# bpod_stepper_1_4_5.net
KiCad netlist of a schematic drawn in EAGLE
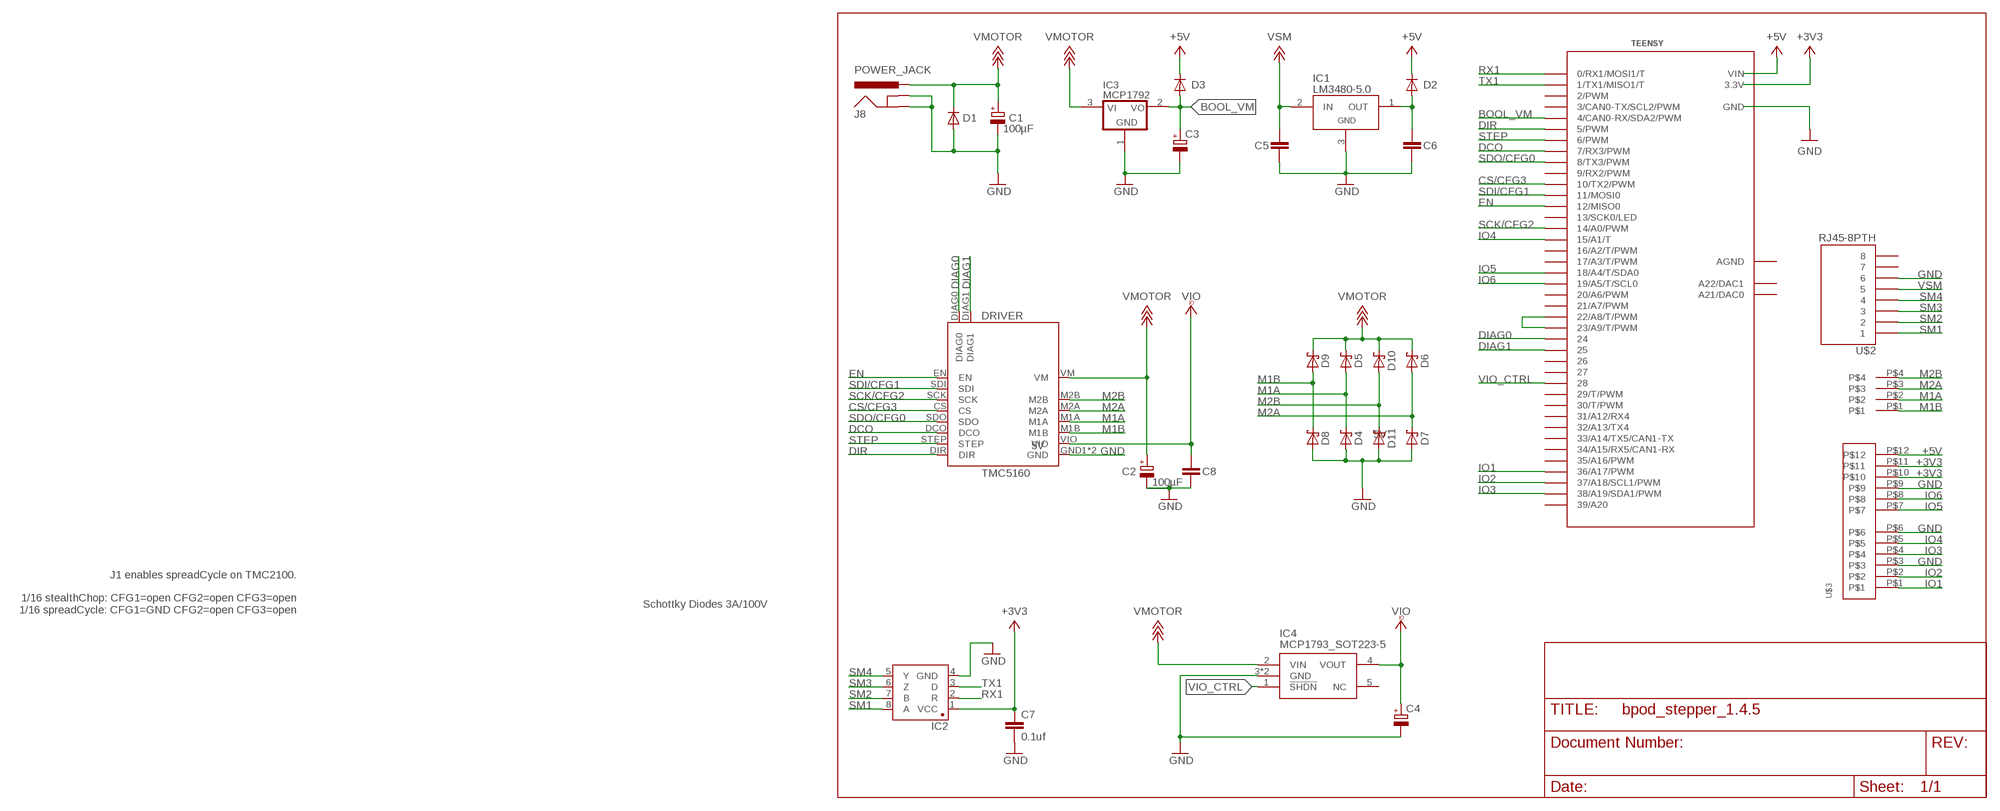
[diagram p0: schematic, sheet 1]

(export (version "E")
  (design (tool "Eeschema 10.0.6"))
  (components
    (comp (ref "C1")
      (value "100µF")
      (footprint "eagle-import:PANASONIC_G")
      (libsource (lib "eagle-import") (part "CPOL-EUG"))
    )
    (comp (ref "C2")
      (value "100µF")
      (footprint "eagle-import:PANASONIC_G")
      (libsource (lib "eagle-import") (part "CPOL-EUG"))
    )
    (comp (ref "C3")
      (value "CPOL-EUB")
      (footprint "eagle-import:PANASONIC_B")
      (libsource (lib "eagle-import") (part "CPOL-EUB"))
    )
    (comp (ref "C4")
      (value "CPOL-EUB")
      (footprint "eagle-import:PANASONIC_B")
      (libsource (lib "eagle-import") (part "CPOL-EUB"))
    )
    (comp (ref "C5")
      (value "0.1uf")
      (footprint "eagle-import:1206@1")
      (libsource (lib "eagle-import") (part "CAP1206"))
    )
    (comp (ref "C6")
      (value "0.1uf")
      (footprint "eagle-import:1206@1")
      (libsource (lib "eagle-import") (part "CAP1206"))
    )
    (comp (ref "C7")
      (value "0.1uf")
      (footprint "eagle-import:1206@1")
      (libsource (lib "eagle-import") (part "CAP1206"))
    )
    (comp (ref "C8")
      (value "100nf")
      (footprint "eagle-import:1206@1")
      (libsource (lib "eagle-import") (part "CAP1206"))
    )
    (comp (ref "D1")
      (value "DIODE-DO214AA")
      (footprint "eagle-import:DO214AA")
      (libsource (lib "eagle-import") (part "DIODE-DO214AA"))
    )
    (comp (ref "D2")
      (value "MBR0520LT")
      (footprint "eagle-import:SOD123")
      (libsource (lib "eagle-import") (part "MBR0520LT"))
    )
    (comp (ref "D3")
      (value "MBR0520LT")
      (footprint "eagle-import:SOD123")
      (libsource (lib "eagle-import") (part "MBR0520LT"))
    )
    (comp (ref "D4")
      (value "S310FA")
      (footprint "eagle-import:SOD123")
      (libsource (lib "eagle-import") (part "D_SCHOTTKY-SOD123"))
    )
    (comp (ref "D5")
      (value "S310FA")
      (footprint "eagle-import:SOD123")
      (libsource (lib "eagle-import") (part "D_SCHOTTKY-SOD123"))
    )
    (comp (ref "D6")
      (value "S310FA")
      (footprint "eagle-import:SOD123")
      (libsource (lib "eagle-import") (part "D_SCHOTTKY-SOD123"))
    )
    (comp (ref "D7")
      (value "S310FA")
      (footprint "eagle-import:SOD123")
      (libsource (lib "eagle-import") (part "D_SCHOTTKY-SOD123"))
    )
    (comp (ref "D8")
      (value "S310FA")
      (footprint "eagle-import:SOD123")
      (libsource (lib "eagle-import") (part "D_SCHOTTKY-SOD123"))
    )
    (comp (ref "D9")
      (value "S310FA")
      (footprint "eagle-import:SOD123")
      (libsource (lib "eagle-import") (part "D_SCHOTTKY-SOD123"))
    )
    (comp (ref "D10")
      (value "S310FA")
      (footprint "eagle-import:SOD123")
      (libsource (lib "eagle-import") (part "D_SCHOTTKY-SOD123"))
    )
    (comp (ref "D11")
      (value "S310FA")
      (footprint "eagle-import:SOD123")
      (libsource (lib "eagle-import") (part "D_SCHOTTKY-SOD123"))
    )
    (comp (ref "DRIVER")
      (value "TMC5160")
      (footprint "eagle-import:TMC5160")
      (libsource (lib "eagle-import") (part "TMC5160"))
    )
    (comp (ref "IC1")
      (value "LM3480-5.0")
      (footprint "eagle-import:SOT-23-3")
      (libsource (lib "eagle-import") (part "LM3480-5.0"))
    )
    (comp (ref "IC2")
      (value "SN65HVD31DR")
      (footprint "eagle-import:SO08")
      (libsource (lib "eagle-import") (part "SN65HVD31DR"))
    )
    (comp (ref "IC3")
      (value "MCP1792")
      (footprint "eagle-import:SOT23A_MICROCHIP_CB")
      (libsource (lib "eagle-import") (part "MCP170302E/CB-12"))
    )
    (comp (ref "IC4")
      (value "MCP1793_SOT223-5")
      (footprint "eagle-import:SOT223-5")
      (libsource (lib "eagle-import") (part "MCP1793_SOT223-5"))
    )
    (comp (ref "J8")
      (value "POWER_JACK")
      (footprint "eagle-import:POWER_JACK_PTH")
      (libsource (lib "eagle-import") (part "POWER_JACK"))
    )
    (comp (ref "TEENSY")
      (value "TEENSY_3.6_DIL")
      (footprint "eagle-import:TEENSY_3.6_DIL")
      (libsource (lib "eagle-import") (part "TEENSY_3.6_DIL"))
    )
    (comp (ref "U$2")
      (value "RJ45-8PTH")
      (footprint "eagle-import:RJ45-8")
      (libsource (lib "eagle-import") (part "RJ45-8PTH"))
    )
    (comp (ref "U$3")
      (value "12POS_MOLEX_SOCKET")
      (footprint "eagle-import:12POS_MOLEX_SOCKET")
      (libsource (lib "eagle-import") (part "12POS_MOLEX_SOCKET"))
    )
    (comp (ref "U$4")
      (value "MOLEX395221004")
      (footprint "eagle-import:MOLEX395221004")
      (libsource (lib "eagle-import") (part "MOLEX395221004"))
    )
  )
  (nets
    (net (code "1") (name "+3V3") (class "Default")
      (node (ref "C7") (pin "1") (pinfunction "1_1") (pintype "passive"))
      (node (ref "IC2") (pin "1") (pinfunction "VCC_1") (pintype "bidirectional"))
      (node (ref "TEENSY") (pin "3.3V") (pinfunction "3.3V_3.3V") (pintype "power_in"))
      (node (ref "TEENSY") (pin "3.3V3") (pinfunction "3.3V_3.3V3") (pintype "power_in"))
      (node (ref "U$3") (pin "P$10") (pinfunction "P$10_P$10") (pintype "bidirectional"))
      (node (ref "U$3") (pin "P$11") (pinfunction "P$11_P$11") (pintype "bidirectional"))
    )
    (net (code "2") (name "+5V") (class "Default")
      (node (ref "D2") (pin "C") (pinfunction "C_C") (pintype "passive"))
      (node (ref "D3") (pin "C") (pinfunction "C_C") (pintype "passive"))
      (node (ref "TEENSY") (pin "VIN") (pinfunction "VIN_VIN") (pintype "power_in"))
      (node (ref "U$3") (pin "P$12") (pinfunction "P$12_P$12") (pintype "bidirectional"))
    )
    (net (code "3") (name "+12V") (class "Default")
      (node (ref "C5") (pin "2") (pinfunction "2_2") (pintype "passive"))
      (node (ref "IC1") (pin "2") (pinfunction "IN_2") (pintype "power_in"))
      (node (ref "U$2") (pin "5") (pinfunction "5_5") (pintype "bidirectional"))
    )
    (net (code "4") (name "+18V") (class "Default")
      (node (ref "C1") (pin "+") (pinfunction "+_+") (pintype "passive"))
      (node (ref "C2") (pin "+") (pinfunction "+_+") (pintype "passive"))
      (node (ref "D1") (pin "C") (pinfunction "C_C") (pintype "passive"))
      (node (ref "D10") (pin "C") (pinfunction "C_C") (pintype "passive"))
      (node (ref "D5") (pin "C") (pinfunction "C_C") (pintype "passive"))
      (node (ref "D6") (pin "C") (pinfunction "C_C") (pintype "passive"))
      (node (ref "D9") (pin "C") (pinfunction "C_C") (pintype "passive"))
      (node (ref "DRIVER") (pin "VM") (pinfunction "VM_VM") (pintype "power_in"))
      (node (ref "IC3") (pin "3") (pinfunction "VI_3") (pintype "power_in"))
      (node (ref "IC4") (pin "2") (pinfunction "VIN_2") (pintype "bidirectional"))
      (node (ref "J8") (pin "PWR") (pinfunction "PWR_PWR") (pintype "bidirectional"))
    )
    (net (code "5") (name "/AGND") (class "Default")
      (node (ref "TEENSY") (pin "AGND") (pinfunction "AGND_AGND") (pintype "power_in"))
    )
    (net (code "6") (name "/CS{slash}CFG3") (class "Default")
      (node (ref "DRIVER") (pin "CS") (pinfunction "CS_CS") (pintype "passive"))
      (node (ref "TEENSY") (pin "10") (pinfunction "10/TX2/PWM_10") (pintype "bidirectional"))
    )
    (net (code "7") (name "/DCO") (class "Default")
      (node (ref "DRIVER") (pin "DCO") (pinfunction "DCO_DCO") (pintype "passive"))
      (node (ref "TEENSY") (pin "7") (pinfunction "7/RX3/PWM_7") (pintype "bidirectional"))
    )
    (net (code "8") (name "/DIAG0") (class "Default")
      (node (ref "DRIVER") (pin "DIAG0") (pinfunction "DIAG0_DIAG0") (pintype "passive"))
      (node (ref "TEENSY") (pin "24") (pinfunction "24_24") (pintype "bidirectional"))
    )
    (net (code "9") (name "/DIAG1") (class "Default")
      (node (ref "DRIVER") (pin "DIAG1") (pinfunction "DIAG1_DIAG1") (pintype "passive"))
      (node (ref "TEENSY") (pin "25") (pinfunction "25_25") (pintype "bidirectional"))
    )
    (net (code "10") (name "/DIR") (class "Default")
      (node (ref "DRIVER") (pin "DIR") (pinfunction "DIR_DIR") (pintype "input"))
      (node (ref "TEENSY") (pin "5") (pinfunction "5/PWM_5") (pintype "bidirectional"))
    )
    (net (code "11") (name "/EN") (class "Default")
      (node (ref "DRIVER") (pin "EN") (pinfunction "EN_EN") (pintype "passive"))
      (node (ref "TEENSY") (pin "12") (pinfunction "12/MISO0_12") (pintype "bidirectional"))
    )
    (net (code "12") (name "/IO1") (class "Default")
      (node (ref "TEENSY") (pin "36/A17") (pinfunction "36/A17/PWM_36/A17") (pintype "bidirectional"))
      (node (ref "U$3") (pin "P$1") (pinfunction "P$1_P$1") (pintype "bidirectional"))
    )
    (net (code "13") (name "/IO2") (class "Default")
      (node (ref "TEENSY") (pin "37/A18") (pinfunction "37/A18/SCL1/PWM_37/A18") (pintype "bidirectional"))
      (node (ref "U$3") (pin "P$2") (pinfunction "P$2_P$2") (pintype "bidirectional"))
    )
    (net (code "14") (name "/IO3") (class "Default")
      (node (ref "TEENSY") (pin "38/A19") (pinfunction "38/A19/SDA1/PWM_38/A19") (pintype "bidirectional"))
      (node (ref "U$3") (pin "P$4") (pinfunction "P$4_P$4") (pintype "bidirectional"))
    )
    (net (code "15") (name "/IO4") (class "Default")
      (node (ref "TEENSY") (pin "15/A1") (pinfunction "15/A1/T_15/A1") (pintype "bidirectional"))
      (node (ref "U$3") (pin "P$5") (pinfunction "P$5_P$5") (pintype "bidirectional"))
    )
    (net (code "16") (name "/IO5") (class "Default")
      (node (ref "TEENSY") (pin "18/A4") (pinfunction "18/A4/T/SDA0_18/A4") (pintype "bidirectional"))
      (node (ref "U$3") (pin "P$7") (pinfunction "P$7_P$7") (pintype "bidirectional"))
    )
    (net (code "17") (name "/IO6") (class "Default")
      (node (ref "TEENSY") (pin "19/A5") (pinfunction "19/A5/T/SCL0_19/A5") (pintype "bidirectional"))
      (node (ref "U$3") (pin "P$8") (pinfunction "P$8_P$8") (pintype "bidirectional"))
    )
    (net (code "18") (name "/M1A") (class "Default")
      (node (ref "D4") (pin "C") (pinfunction "C_C") (pintype "passive"))
      (node (ref "D5") (pin "A") (pinfunction "A_A") (pintype "passive"))
      (node (ref "DRIVER") (pin "M1A") (pinfunction "M1A_M1A") (pintype "output"))
      (node (ref "U$4") (pin "P$2") (pinfunction "P$2_P$2") (pintype "bidirectional"))
    )
    (net (code "19") (name "/M1B") (class "Default")
      (node (ref "D8") (pin "C") (pinfunction "C_C") (pintype "passive"))
      (node (ref "D9") (pin "A") (pinfunction "A_A") (pintype "passive"))
      (node (ref "DRIVER") (pin "M1B") (pinfunction "M1B_M1B") (pintype "output"))
      (node (ref "U$4") (pin "P$1") (pinfunction "P$1_P$1") (pintype "bidirectional"))
    )
    (net (code "20") (name "/M2A") (class "Default")
      (node (ref "D6") (pin "A") (pinfunction "A_A") (pintype "passive"))
      (node (ref "D7") (pin "C") (pinfunction "C_C") (pintype "passive"))
      (node (ref "DRIVER") (pin "M2A") (pinfunction "M2A_M2A") (pintype "output"))
      (node (ref "U$4") (pin "P$3") (pinfunction "P$3_P$3") (pintype "bidirectional"))
    )
    (net (code "21") (name "/M2B") (class "Default")
      (node (ref "D10") (pin "A") (pinfunction "A_A") (pintype "passive"))
      (node (ref "D11") (pin "C") (pinfunction "C_C") (pintype "passive"))
      (node (ref "DRIVER") (pin "M2B") (pinfunction "M2B_M2B") (pintype "output"))
      (node (ref "U$4") (pin "P$4") (pinfunction "P$4_P$4") (pintype "bidirectional"))
    )
    (net (code "22") (name "/RX1") (class "Default")
      (node (ref "IC2") (pin "2") (pinfunction "R_2") (pintype "bidirectional"))
      (node (ref "TEENSY") (pin "0") (pinfunction "0/RX1/MOSI1/T_0") (pintype "bidirectional"))
    )
    (net (code "23") (name "/SCK{slash}CFG2") (class "Default")
      (node (ref "DRIVER") (pin "SCK") (pinfunction "SCK_SCK") (pintype "passive"))
      (node (ref "TEENSY") (pin "14/A0") (pinfunction "14/A0/PWM_14/A0") (pintype "bidirectional"))
    )
    (net (code "24") (name "/SDI{slash}CFG1") (class "Default")
      (node (ref "DRIVER") (pin "SDI") (pinfunction "SDI_SDI") (pintype "passive"))
      (node (ref "TEENSY") (pin "11") (pinfunction "11/MOSI0_11") (pintype "bidirectional"))
    )
    (net (code "25") (name "/SDO{slash}CFG0") (class "Default")
      (node (ref "DRIVER") (pin "SDO") (pinfunction "SDO_SDO") (pintype "passive"))
      (node (ref "TEENSY") (pin "8") (pinfunction "8/TX3/PWM_8") (pintype "bidirectional"))
    )
    (net (code "26") (name "/SM1") (class "Default")
      (node (ref "IC2") (pin "8") (pinfunction "A_8") (pintype "bidirectional"))
      (node (ref "U$2") (pin "1") (pinfunction "1_1") (pintype "bidirectional"))
    )
    (net (code "27") (name "/SM2") (class "Default")
      (node (ref "IC2") (pin "7") (pinfunction "B_7") (pintype "bidirectional"))
      (node (ref "U$2") (pin "2") (pinfunction "2_2") (pintype "bidirectional"))
    )
    (net (code "28") (name "/SM3") (class "Default")
      (node (ref "IC2") (pin "6") (pinfunction "Z_6") (pintype "bidirectional"))
      (node (ref "U$2") (pin "3") (pinfunction "3_3") (pintype "bidirectional"))
    )
    (net (code "29") (name "/SM4") (class "Default")
      (node (ref "IC2") (pin "5") (pinfunction "Y_5") (pintype "bidirectional"))
      (node (ref "U$2") (pin "4") (pinfunction "4_4") (pintype "bidirectional"))
    )
    (net (code "30") (name "/STEP") (class "Default")
      (node (ref "DRIVER") (pin "STEP") (pinfunction "STEP_STEP") (pintype "input"))
      (node (ref "TEENSY") (pin "6") (pinfunction "6/PWM_6") (pintype "bidirectional"))
    )
    (net (code "31") (name "/TX1") (class "Default")
      (node (ref "IC2") (pin "3") (pinfunction "D_3") (pintype "bidirectional"))
      (node (ref "TEENSY") (pin "1") (pinfunction "1/TX1/MISO1/T_1") (pintype "bidirectional"))
    )
    (net (code "32") (name "BOOL_VM") (class "Default")
      (node (ref "C3") (pin "+") (pinfunction "+_+") (pintype "passive"))
      (node (ref "D3") (pin "A") (pinfunction "A_A") (pintype "passive"))
      (node (ref "IC3") (pin "2") (pinfunction "VO_2") (pintype "passive"))
      (node (ref "TEENSY") (pin "4") (pinfunction "4/CAN0-RX/SDA2/PWM_4") (pintype "bidirectional"))
    )
    (net (code "33") (name "GND") (class "Default")
      (node (ref "C1") (pin "-") (pinfunction "-_-") (pintype "passive"))
      (node (ref "C2") (pin "-") (pinfunction "-_-") (pintype "passive"))
      (node (ref "C3") (pin "-") (pinfunction "-_-") (pintype "passive"))
      (node (ref "C4") (pin "-") (pinfunction "-_-") (pintype "passive"))
      (node (ref "C5") (pin "1") (pinfunction "1_1") (pintype "passive"))
      (node (ref "C6") (pin "1") (pinfunction "1_1") (pintype "passive"))
      (node (ref "C7") (pin "2") (pinfunction "2_2") (pintype "passive"))
      (node (ref "C8") (pin "2") (pinfunction "2_2") (pintype "passive"))
      (node (ref "D1") (pin "A") (pinfunction "A_A") (pintype "passive"))
      (node (ref "D11") (pin "A") (pinfunction "A_A") (pintype "passive"))
      (node (ref "D4") (pin "A") (pinfunction "A_A") (pintype "passive"))
      (node (ref "D7") (pin "A") (pinfunction "A_A") (pintype "passive"))
      (node (ref "D8") (pin "A") (pinfunction "A_A") (pintype "passive"))
      (node (ref "DRIVER") (pin "GND1") (pinfunction "GND_GND1") (pintype "power_in"))
      (node (ref "DRIVER") (pin "GND2") (pinfunction "GND_GND2") (pintype "power_in"))
      (node (ref "IC1") (pin "3") (pinfunction "GND_3") (pintype "power_in"))
      (node (ref "IC2") (pin "4") (pinfunction "GND_4") (pintype "bidirectional"))
      (node (ref "IC3") (pin "1") (pinfunction "GND_1") (pintype "power_in"))
      (node (ref "IC4") (pin "3") (pinfunction "GND_3") (pintype "bidirectional"))
      (node (ref "IC4") (pin "6") (pinfunction "GND_6") (pintype "bidirectional"))
      (node (ref "J8") (pin "GND") (pinfunction "GND_GND") (pintype "bidirectional"))
      (node (ref "J8") (pin "GNDBREAK") (pinfunction "GNDBREAK_GNDBREAK") (pintype "bidirectional"))
      (node (ref "TEENSY") (pin "GND") (pinfunction "GND_GND") (pintype "power_in"))
      (node (ref "TEENSY") (pin "GND1") (pinfunction "GND_GND1") (pintype "power_in"))
      (node (ref "U$2") (pin "6") (pinfunction "6_6") (pintype "bidirectional"))
      (node (ref "U$3") (pin "P$3") (pinfunction "P$3_P$3") (pintype "bidirectional"))
      (node (ref "U$3") (pin "P$6") (pinfunction "P$6_P$6") (pintype "bidirectional"))
      (node (ref "U$3") (pin "P$9") (pinfunction "P$9_P$9") (pintype "bidirectional"))
    )
    (net (code "34") (name "Net-(IC1-OUT)") (class "Default")
      (node (ref "C6") (pin "2") (pinfunction "2_2") (pintype "passive"))
      (node (ref "D2") (pin "A") (pinfunction "A_A") (pintype "passive"))
      (node (ref "IC1") (pin "1") (pinfunction "OUT_1") (pintype "power_in"))
    )
    (net (code "35") (name "Net-(TEENSY-22{slash}A8{slash}T{slash}PWM)") (class "Default")
      (node (ref "TEENSY") (pin "22/A8") (pinfunction "22/A8/T/PWM_22/A8") (pintype "bidirectional"))
      (node (ref "TEENSY") (pin "23/A9") (pinfunction "23/A9/T/PWM_23/A9") (pintype "bidirectional"))
    )
    (net (code "36") (name "VCCIO") (class "Default")
      (node (ref "C4") (pin "+") (pinfunction "+_+") (pintype "passive"))
      (node (ref "C8") (pin "1") (pinfunction "1_1") (pintype "passive"))
      (node (ref "DRIVER") (pin "VIO") (pinfunction "VIO_VIO") (pintype "power_in"))
      (node (ref "IC4") (pin "4") (pinfunction "VOUT_4") (pintype "bidirectional"))
    )
    (net (code "37") (name "VIO_CTRL") (class "Default")
      (node (ref "IC4") (pin "1") (pinfunction "~{SHDN}_1") (pintype "bidirectional"))
      (node (ref "TEENSY") (pin "28") (pinfunction "28_28") (pintype "bidirectional"))
    )
    (net (code "38") (name "unconnected-(IC4-NC-Pad5)") (class "Default")
      (node (ref "IC4") (pin "5") (pinfunction "NC_5") (pintype "bidirectional"))
    )
    (net (code "39") (name "unconnected-(TEENSY-2{slash}PWM-Pad2)") (class "Default")
      (node (ref "TEENSY") (pin "2") (pinfunction "2/PWM_2") (pintype "bidirectional"))
    )
    (net (code "40") (name "unconnected-(TEENSY-3{slash}CAN0-TX{slash}SCL2{slash}PWM-Pad3)") (class "Default")
      (node (ref "TEENSY") (pin "3") (pinfunction "3/CAN0-TX/SCL2/PWM_3") (pintype "bidirectional"))
    )
    (net (code "41") (name "unconnected-(TEENSY-9{slash}RX2{slash}PWM-Pad9)") (class "Default")
      (node (ref "TEENSY") (pin "9") (pinfunction "9/RX2/PWM_9") (pintype "bidirectional"))
    )
    (net (code "42") (name "unconnected-(TEENSY-13{slash}SCK0{slash}LED-Pad13)") (class "Default")
      (node (ref "TEENSY") (pin "13") (pinfunction "13/SCK0/LED_13") (pintype "bidirectional"))
    )
    (net (code "43") (name "unconnected-(TEENSY-16{slash}A2{slash}T{slash}PWM-Pad16{slash}A2)") (class "Default")
      (node (ref "TEENSY") (pin "16/A2") (pinfunction "16/A2/T/PWM_16/A2") (pintype "bidirectional"))
    )
    (net (code "44") (name "unconnected-(TEENSY-17{slash}A3{slash}T{slash}PWM-Pad17{slash}A3)") (class "Default")
      (node (ref "TEENSY") (pin "17/A3") (pinfunction "17/A3/T/PWM_17/A3") (pintype "bidirectional"))
    )
    (net (code "45") (name "unconnected-(TEENSY-20{slash}A6{slash}PWM-Pad20{slash}A6)") (class "Default")
      (node (ref "TEENSY") (pin "20/A6") (pinfunction "20/A6/PWM_20/A6") (pintype "bidirectional"))
    )
    (net (code "46") (name "unconnected-(TEENSY-21{slash}A7{slash}PWM-Pad21{slash}A7)") (class "Default")
      (node (ref "TEENSY") (pin "21/A7") (pinfunction "21/A7/PWM_21/A7") (pintype "bidirectional"))
    )
    (net (code "47") (name "unconnected-(TEENSY-29{slash}T{slash}PWM-Pad29)") (class "Default")
      (node (ref "TEENSY") (pin "29") (pinfunction "29/T/PWM_29") (pintype "bidirectional"))
    )
    (net (code "48") (name "unconnected-(TEENSY-30{slash}T{slash}PWM-Pad30)") (class "Default")
      (node (ref "TEENSY") (pin "30") (pinfunction "30/T/PWM_30") (pintype "bidirectional"))
    )
    (net (code "49") (name "unconnected-(TEENSY-31{slash}A12{slash}RX4-Pad31{slash}A12)") (class "Default")
      (node (ref "TEENSY") (pin "31/A12") (pinfunction "31/A12/RX4_31/A12") (pintype "bidirectional"))
    )
    (net (code "50") (name "unconnected-(TEENSY-32{slash}A13{slash}TX4-Pad32{slash}A13)") (class "Default")
      (node (ref "TEENSY") (pin "32/A13") (pinfunction "32/A13/TX4_32/A13") (pintype "bidirectional"))
    )
    (net (code "51") (name "unconnected-(TEENSY-33{slash}A14{slash}TX5{slash}CAN1-TX-Pad33{slash}A14)") (class "Default")
      (node (ref "TEENSY") (pin "33/A14") (pinfunction "33/A14/TX5/CAN1-TX_33/A14") (pintype "bidirectional"))
    )
    (net (code "52") (name "unconnected-(TEENSY-34{slash}A15{slash}RX5{slash}CAN1-RX-Pad34{slash}A15)") (class "Default")
      (node (ref "TEENSY") (pin "34/A15") (pinfunction "34/A15/RX5/CAN1-RX_34/A15") (pintype "bidirectional"))
    )
    (net (code "53") (name "unconnected-(TEENSY-35{slash}A16{slash}PWM-Pad35{slash}A16)") (class "Default")
      (node (ref "TEENSY") (pin "35/A16") (pinfunction "35/A16/PWM_35/A16") (pintype "bidirectional"))
    )
    (net (code "54") (name "unconnected-(TEENSY-A21{slash}DAC0-PadA21)") (class "Default")
      (node (ref "TEENSY") (pin "A21") (pinfunction "A21/DAC0_A21") (pintype "bidirectional"))
    )
    (net (code "55") (name "unconnected-(TEENSY-A22{slash}DAC1-PadA22)") (class "Default")
      (node (ref "TEENSY") (pin "A22") (pinfunction "A22/DAC1_A22") (pintype "bidirectional"))
    )
    (net (code "56") (name "unconnected-(TEENSY-Pad26)") (class "Default")
      (node (ref "TEENSY") (pin "26") (pinfunction "26_26") (pintype "bidirectional"))
    )
    (net (code "57") (name "unconnected-(TEENSY-Pad27)") (class "Default")
      (node (ref "TEENSY") (pin "27") (pinfunction "27_27") (pintype "bidirectional"))
    )
    (net (code "58") (name "unconnected-(TEENSY-Pad39{slash}A20)") (class "Default")
      (node (ref "TEENSY") (pin "39/A20") (pinfunction "39/A20_39/A20") (pintype "bidirectional"))
    )
    (net (code "59") (name "unconnected-(U$2-Pad7)") (class "Default")
      (node (ref "U$2") (pin "7") (pinfunction "7_7") (pintype "bidirectional"))
    )
    (net (code "60") (name "unconnected-(U$2-Pad8)") (class "Default")
      (node (ref "U$2") (pin "8") (pinfunction "8_8") (pintype "bidirectional"))
    )
  )
)
